# Eagle_CAD_XO_game.net
KiCad netlist of a schematic drawn in EAGLE
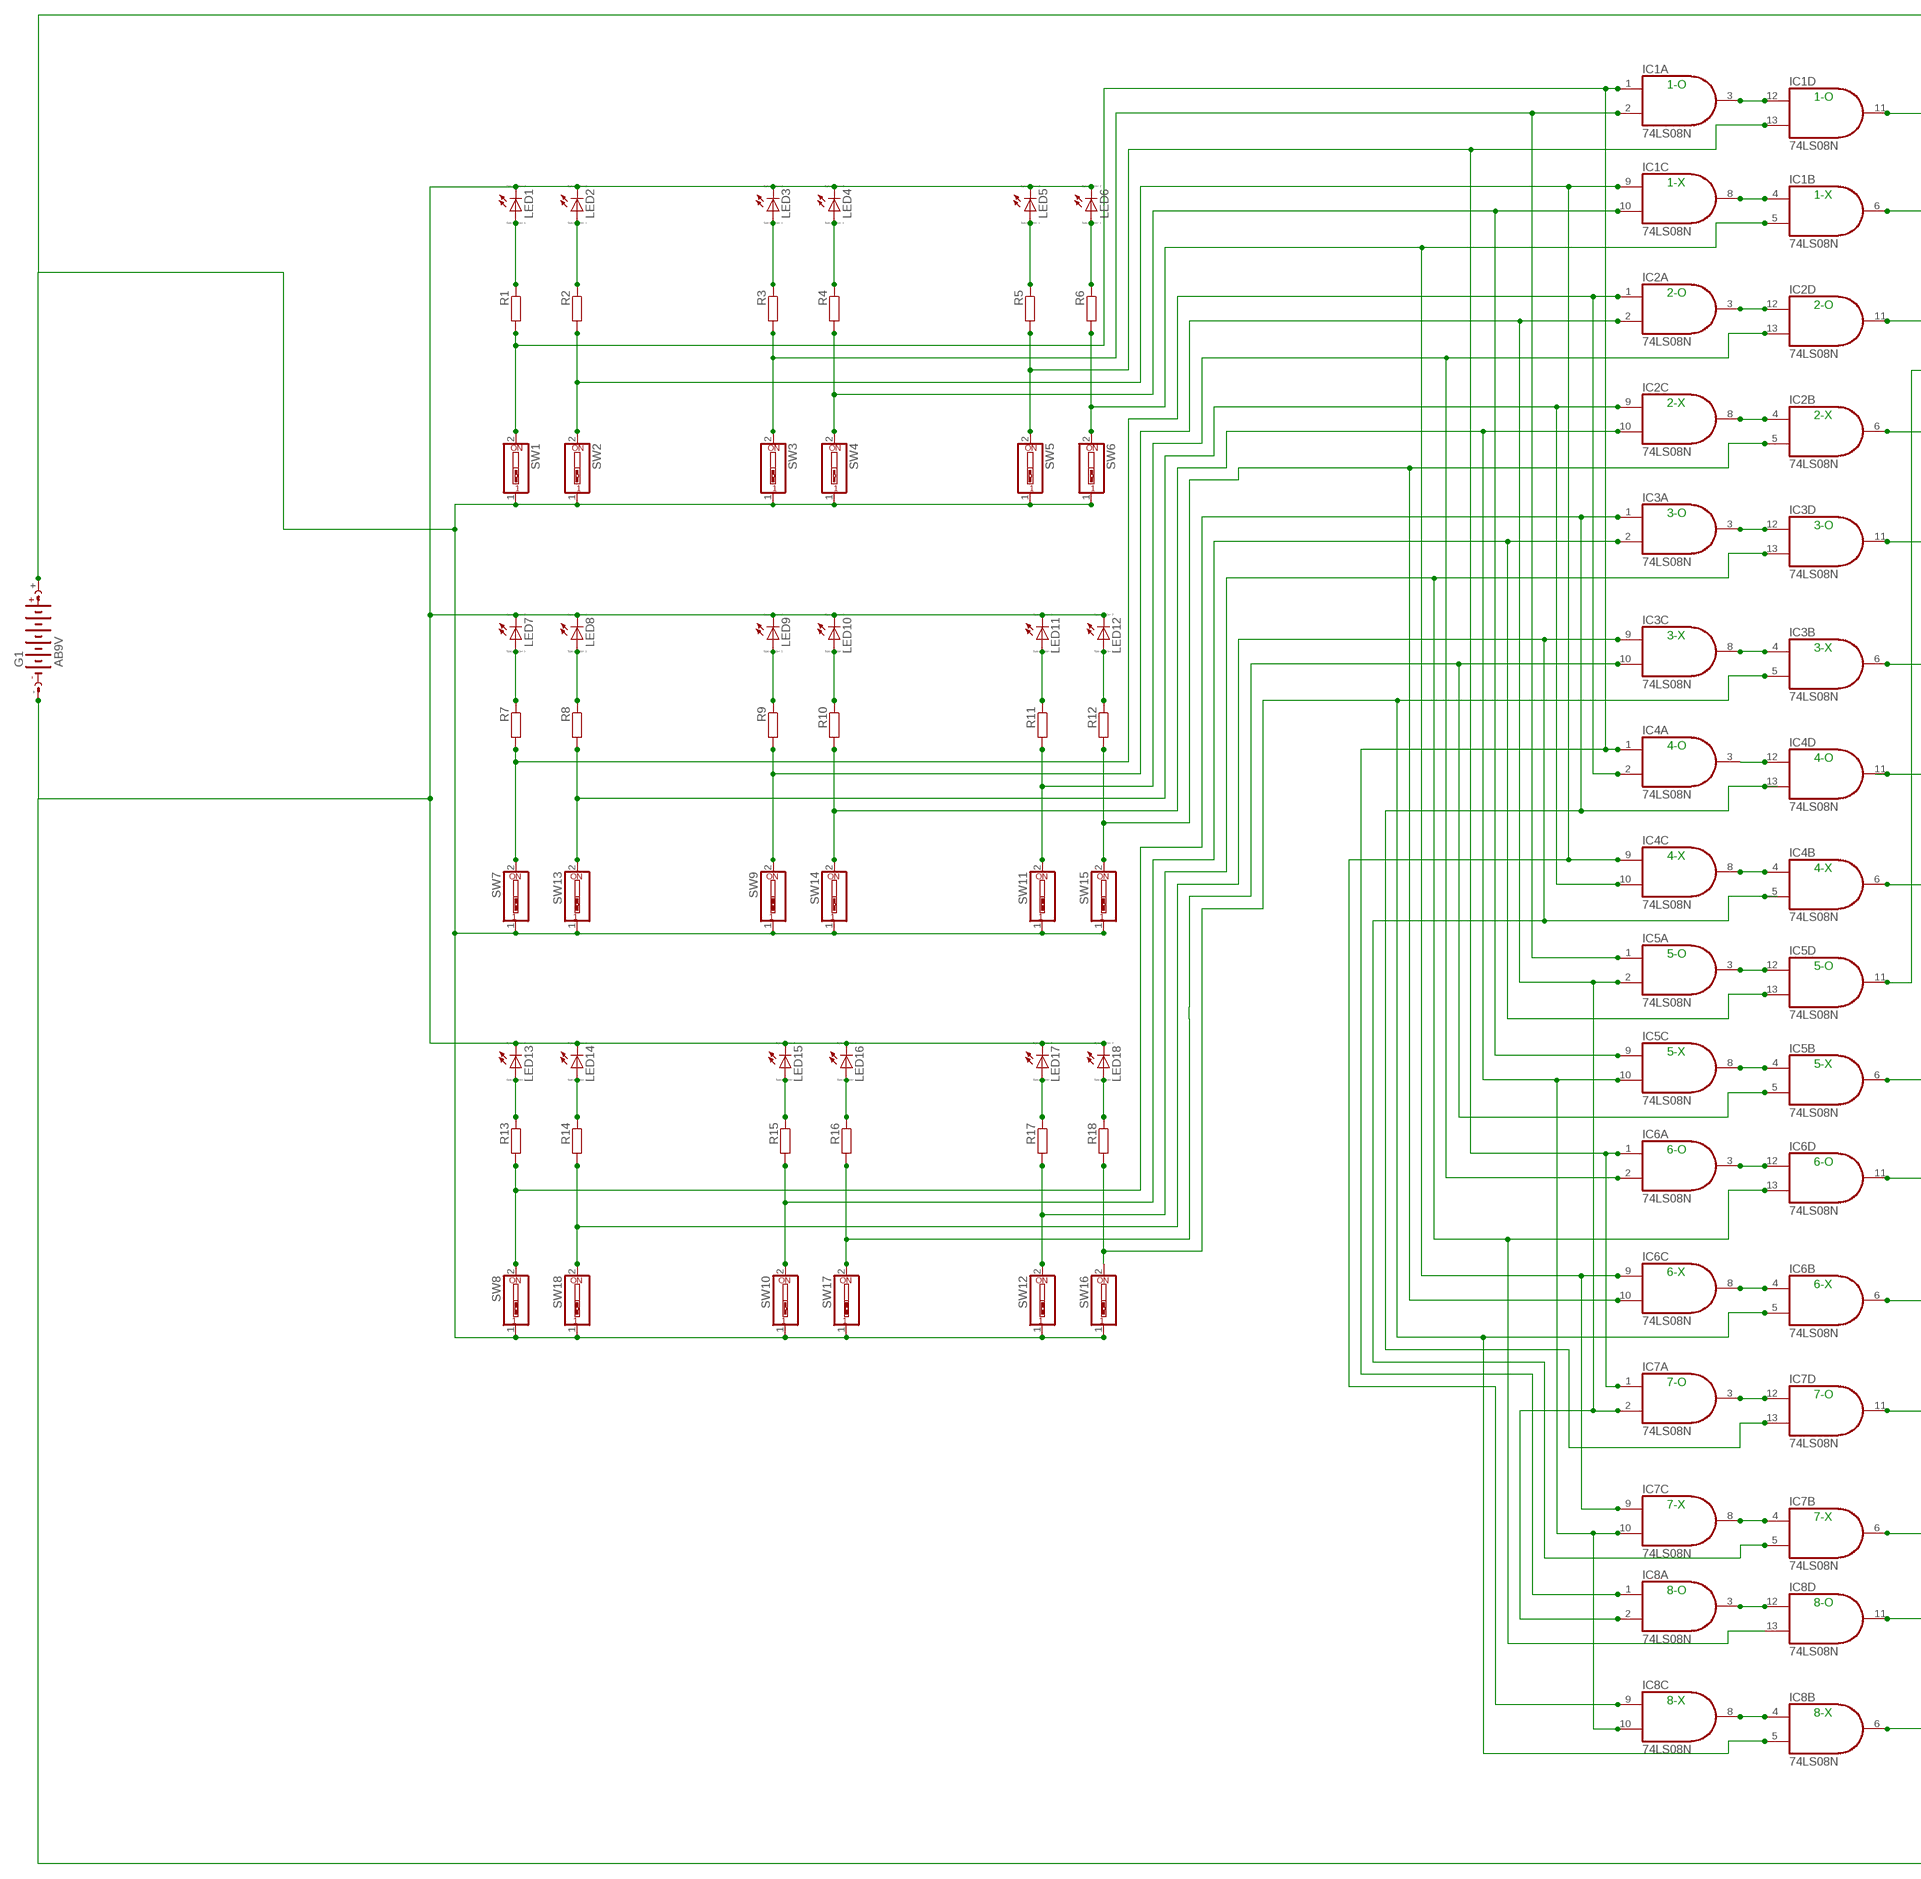
[diagram p0: schematic, sheet 1, part 1 of 2]
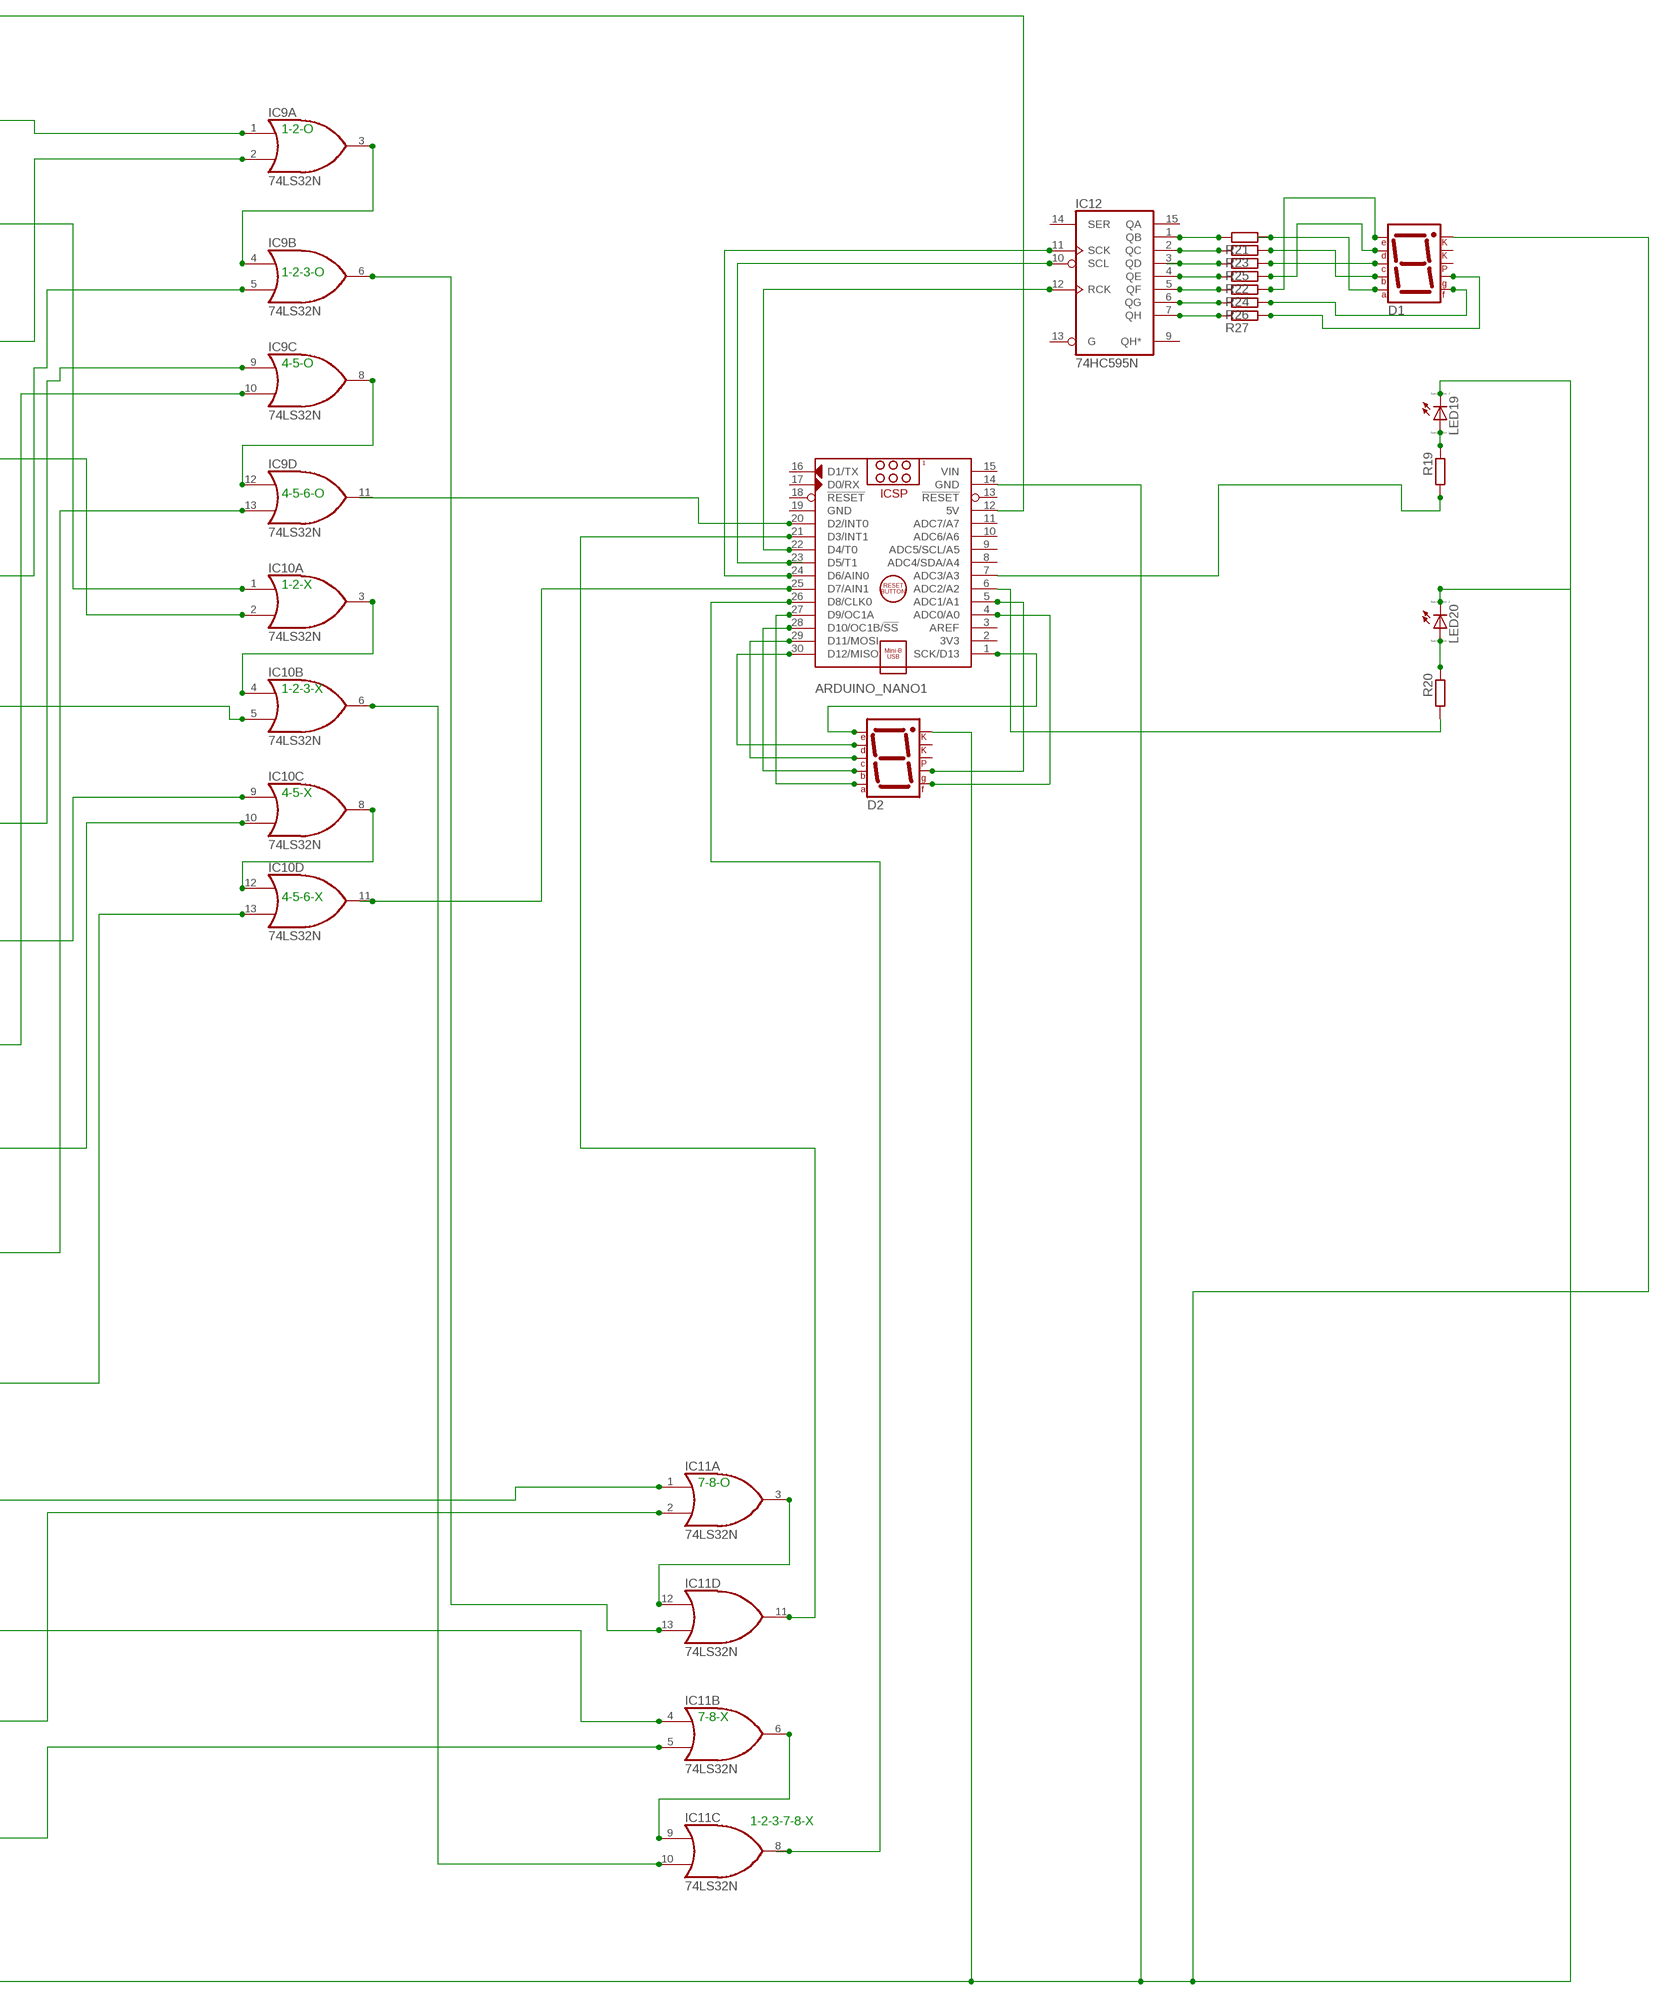
[diagram p1: schematic, sheet 1, part 2 of 2]

(export (version "E")
  (design (tool "Eeschema 10.0.6"))
  (components
    (comp (ref "ARDUINO_NANO1")
      (value "ARDUINO_NANO")
      (footprint "eagle-import:ARDUINO_NANO")
      (libsource (lib "eagle-import") (part "ARDUINO_NANO"))
    )
    (comp (ref "D1")
      (value "7SEG-CK")
      (footprint "eagle-import:7SEG-13")
      (libsource (lib "eagle-import") (part "7SEG-CK"))
    )
    (comp (ref "D2")
      (value "7SEG-CK")
      (footprint "eagle-import:7SEG-13")
      (libsource (lib "eagle-import") (part "7SEG-CK"))
    )
    (comp (ref "G1")
      (value "AB9V")
      (footprint "eagle-import:AB9V")
      (libsource (lib "eagle-import") (part "AB9V"))
    )
    (comp (ref "IC1")
      (value "74LS08N")
      (footprint "eagle-import:DIL14")
      (libsource (lib "eagle-import") (part "7408NLS"))
    )
    (comp (ref "IC2")
      (value "74LS08N")
      (footprint "eagle-import:DIL14")
      (libsource (lib "eagle-import") (part "7408NLS"))
    )
    (comp (ref "IC3")
      (value "74LS08N")
      (footprint "eagle-import:DIL14")
      (libsource (lib "eagle-import") (part "7408NLS"))
    )
    (comp (ref "IC4")
      (value "74LS08N")
      (footprint "eagle-import:DIL14")
      (libsource (lib "eagle-import") (part "7408NLS"))
    )
    (comp (ref "IC5")
      (value "74LS08N")
      (footprint "eagle-import:DIL14")
      (libsource (lib "eagle-import") (part "7408NLS"))
    )
    (comp (ref "IC6")
      (value "74LS08N")
      (footprint "eagle-import:DIL14")
      (libsource (lib "eagle-import") (part "7408NLS"))
    )
    (comp (ref "IC7")
      (value "74LS08N")
      (footprint "eagle-import:DIL14")
      (libsource (lib "eagle-import") (part "7408NLS"))
    )
    (comp (ref "IC8")
      (value "74LS08N")
      (footprint "eagle-import:DIL14")
      (libsource (lib "eagle-import") (part "7408NLS"))
    )
    (comp (ref "IC9")
      (value "74LS32N")
      (footprint "eagle-import:DIL14")
      (libsource (lib "eagle-import") (part "7432NLS"))
    )
    (comp (ref "IC10")
      (value "74LS32N")
      (footprint "eagle-import:DIL14")
      (libsource (lib "eagle-import") (part "7432NLS"))
    )
    (comp (ref "IC11")
      (value "74LS32N")
      (footprint "eagle-import:DIL14")
      (libsource (lib "eagle-import") (part "7432NLS"))
    )
    (comp (ref "IC12")
      (value "74HC595N")
      (footprint "eagle-import:DIL16")
      (libsource (lib "eagle-import") (part "74595NHC"))
    )
    (comp (ref "LED1")
      (value "LED_ELD260")
      (footprint "eagle-import:LED_LD260")
      (libsource (lib "eagle-import") (part "LED_ELD260"))
    )
    (comp (ref "LED2")
      (value "LED_ELD260")
      (footprint "eagle-import:LED_LD260")
      (libsource (lib "eagle-import") (part "LED_ELD260"))
    )
    (comp (ref "LED3")
      (value "LED_ELD260")
      (footprint "eagle-import:LED_LD260")
      (libsource (lib "eagle-import") (part "LED_ELD260"))
    )
    (comp (ref "LED4")
      (value "LED_ELD260")
      (footprint "eagle-import:LED_LD260")
      (libsource (lib "eagle-import") (part "LED_ELD260"))
    )
    (comp (ref "LED5")
      (value "LED_ELD260")
      (footprint "eagle-import:LED_LD260")
      (libsource (lib "eagle-import") (part "LED_ELD260"))
    )
    (comp (ref "LED6")
      (value "LED_ELD260")
      (footprint "eagle-import:LED_LD260")
      (libsource (lib "eagle-import") (part "LED_ELD260"))
    )
    (comp (ref "LED7")
      (value "LED_ELD260")
      (footprint "eagle-import:LED_LD260")
      (libsource (lib "eagle-import") (part "LED_ELD260"))
    )
    (comp (ref "LED8")
      (value "LED_ELD260")
      (footprint "eagle-import:LED_LD260")
      (libsource (lib "eagle-import") (part "LED_ELD260"))
    )
    (comp (ref "LED9")
      (value "LED_ELD260")
      (footprint "eagle-import:LED_LD260")
      (libsource (lib "eagle-import") (part "LED_ELD260"))
    )
    (comp (ref "LED10")
      (value "LED_ELD260")
      (footprint "eagle-import:LED_LD260")
      (libsource (lib "eagle-import") (part "LED_ELD260"))
    )
    (comp (ref "LED11")
      (value "LED_ELD260")
      (footprint "eagle-import:LED_LD260")
      (libsource (lib "eagle-import") (part "LED_ELD260"))
    )
    (comp (ref "LED12")
      (value "LED_ELD260")
      (footprint "eagle-import:LED_LD260")
      (libsource (lib "eagle-import") (part "LED_ELD260"))
    )
    (comp (ref "LED13")
      (value "LED_ELD260")
      (footprint "eagle-import:LED_LD260")
      (libsource (lib "eagle-import") (part "LED_ELD260"))
    )
    (comp (ref "LED14")
      (value "LED_ELD260")
      (footprint "eagle-import:LED_LD260")
      (libsource (lib "eagle-import") (part "LED_ELD260"))
    )
    (comp (ref "LED15")
      (value "LED_ELD260")
      (footprint "eagle-import:LED_LD260")
      (libsource (lib "eagle-import") (part "LED_ELD260"))
    )
    (comp (ref "LED16")
      (value "LED_ELD260")
      (footprint "eagle-import:LED_LD260")
      (libsource (lib "eagle-import") (part "LED_ELD260"))
    )
    (comp (ref "LED17")
      (value "LED_ELD260")
      (footprint "eagle-import:LED_LD260")
      (libsource (lib "eagle-import") (part "LED_ELD260"))
    )
    (comp (ref "LED18")
      (value "LED_ELD260")
      (footprint "eagle-import:LED_LD260")
      (libsource (lib "eagle-import") (part "LED_ELD260"))
    )
    (comp (ref "LED19")
      (value "LED_ELD260")
      (footprint "eagle-import:LED_LD260")
      (libsource (lib "eagle-import") (part "LED_ELD260"))
    )
    (comp (ref "LED20")
      (value "LED_ELD260")
      (footprint "eagle-import:LED_LD260")
      (libsource (lib "eagle-import") (part "LED_ELD260"))
    )
    (comp (ref "R1")
      (value "R-EU_0204/7")
      (footprint "eagle-import:0204_7")
      (libsource (lib "eagle-import") (part "R-EU_0204/7"))
    )
    (comp (ref "R2")
      (value "R-EU_0204/7")
      (footprint "eagle-import:0204_7")
      (libsource (lib "eagle-import") (part "R-EU_0204/7"))
    )
    (comp (ref "R3")
      (value "R-EU_0204/7")
      (footprint "eagle-import:0204_7")
      (libsource (lib "eagle-import") (part "R-EU_0204/7"))
    )
    (comp (ref "R4")
      (value "R-EU_0204/7")
      (footprint "eagle-import:0204_7")
      (libsource (lib "eagle-import") (part "R-EU_0204/7"))
    )
    (comp (ref "R5")
      (value "R-EU_0204/7")
      (footprint "eagle-import:0204_7")
      (libsource (lib "eagle-import") (part "R-EU_0204/7"))
    )
    (comp (ref "R6")
      (value "R-EU_0204/7")
      (footprint "eagle-import:0204_7")
      (libsource (lib "eagle-import") (part "R-EU_0204/7"))
    )
    (comp (ref "R7")
      (value "R-EU_0204/7")
      (footprint "eagle-import:0204_7")
      (libsource (lib "eagle-import") (part "R-EU_0204/7"))
    )
    (comp (ref "R8")
      (value "R-EU_0204/7")
      (footprint "eagle-import:0204_7")
      (libsource (lib "eagle-import") (part "R-EU_0204/7"))
    )
    (comp (ref "R9")
      (value "R-EU_0204/7")
      (footprint "eagle-import:0204_7")
      (libsource (lib "eagle-import") (part "R-EU_0204/7"))
    )
    (comp (ref "R10")
      (value "R-EU_0204/7")
      (footprint "eagle-import:0204_7")
      (libsource (lib "eagle-import") (part "R-EU_0204/7"))
    )
    (comp (ref "R11")
      (value "R-EU_0204/7")
      (footprint "eagle-import:0204_7")
      (libsource (lib "eagle-import") (part "R-EU_0204/7"))
    )
    (comp (ref "R12")
      (value "R-EU_0204/7")
      (footprint "eagle-import:0204_7")
      (libsource (lib "eagle-import") (part "R-EU_0204/7"))
    )
    (comp (ref "R13")
      (value "R-EU_0204/7")
      (footprint "eagle-import:0204_7")
      (libsource (lib "eagle-import") (part "R-EU_0204/7"))
    )
    (comp (ref "R14")
      (value "R-EU_0204/7")
      (footprint "eagle-import:0204_7")
      (libsource (lib "eagle-import") (part "R-EU_0204/7"))
    )
    (comp (ref "R15")
      (value "R-EU_0204/7")
      (footprint "eagle-import:0204_7")
      (libsource (lib "eagle-import") (part "R-EU_0204/7"))
    )
    (comp (ref "R16")
      (value "R-EU_0204/7")
      (footprint "eagle-import:0204_7")
      (libsource (lib "eagle-import") (part "R-EU_0204/7"))
    )
    (comp (ref "R17")
      (value "R-EU_0204/7")
      (footprint "eagle-import:0204_7")
      (libsource (lib "eagle-import") (part "R-EU_0204/7"))
    )
    (comp (ref "R18")
      (value "R-EU_0204/7")
      (footprint "eagle-import:0204_7")
      (libsource (lib "eagle-import") (part "R-EU_0204/7"))
    )
    (comp (ref "R19")
      (value "R-EU_0204/7")
      (footprint "eagle-import:0204_7")
      (libsource (lib "eagle-import") (part "R-EU_0204/7"))
    )
    (comp (ref "R20")
      (value "R-EU_0204/7")
      (footprint "eagle-import:0204_7")
      (libsource (lib "eagle-import") (part "R-EU_0204/7"))
    )
    (comp (ref "R21")
      (value "R-EU_0204/7")
      (footprint "eagle-import:0204_7")
      (libsource (lib "eagle-import") (part "R-EU_0204/7"))
    )
    (comp (ref "R22")
      (value "R-EU_0204/7")
      (footprint "eagle-import:0204_7")
      (libsource (lib "eagle-import") (part "R-EU_0204/7"))
    )
    (comp (ref "R23")
      (value "R-EU_0204/7")
      (footprint "eagle-import:0204_7")
      (libsource (lib "eagle-import") (part "R-EU_0204/7"))
    )
    (comp (ref "R24")
      (value "R-EU_0204/7")
      (footprint "eagle-import:0204_7")
      (libsource (lib "eagle-import") (part "R-EU_0204/7"))
    )
    (comp (ref "R25")
      (value "R-EU_0204/7")
      (footprint "eagle-import:0204_7")
      (libsource (lib "eagle-import") (part "R-EU_0204/7"))
    )
    (comp (ref "R26")
      (value "R-EU_0204/7")
      (footprint "eagle-import:0204_7")
      (libsource (lib "eagle-import") (part "R-EU_0204/7"))
    )
    (comp (ref "R27")
      (value "R-EU_0204/7")
      (footprint "eagle-import:0204_7")
      (libsource (lib "eagle-import") (part "R-EU_0204/7"))
    )
    (comp (ref "SW1")
      (value "SW_DIP-1")
      (footprint "eagle-import:EDG-01")
      (libsource (lib "eagle-import") (part "SW_DIP-1"))
    )
    (comp (ref "SW2")
      (value "SW_DIP-1")
      (footprint "eagle-import:EDG-01")
      (libsource (lib "eagle-import") (part "SW_DIP-1"))
    )
    (comp (ref "SW3")
      (value "SW_DIP-1")
      (footprint "eagle-import:EDG-01")
      (libsource (lib "eagle-import") (part "SW_DIP-1"))
    )
    (comp (ref "SW4")
      (value "SW_DIP-1")
      (footprint "eagle-import:EDG-01")
      (libsource (lib "eagle-import") (part "SW_DIP-1"))
    )
    (comp (ref "SW5")
      (value "SW_DIP-1")
      (footprint "eagle-import:EDG-01")
      (libsource (lib "eagle-import") (part "SW_DIP-1"))
    )
    (comp (ref "SW6")
      (value "SW_DIP-1")
      (footprint "eagle-import:EDG-01")
      (libsource (lib "eagle-import") (part "SW_DIP-1"))
    )
    (comp (ref "SW7")
      (value "SW_DIP-1")
      (footprint "eagle-import:EDG-01")
      (libsource (lib "eagle-import") (part "SW_DIP-1"))
    )
    (comp (ref "SW8")
      (value "SW_DIP-1")
      (footprint "eagle-import:EDG-01")
      (libsource (lib "eagle-import") (part "SW_DIP-1"))
    )
    (comp (ref "SW9")
      (value "SW_DIP-1")
      (footprint "eagle-import:EDG-01")
      (libsource (lib "eagle-import") (part "SW_DIP-1"))
    )
    (comp (ref "SW10")
      (value "SW_DIP-1")
      (footprint "eagle-import:EDG-01")
      (libsource (lib "eagle-import") (part "SW_DIP-1"))
    )
    (comp (ref "SW11")
      (value "SW_DIP-1")
      (footprint "eagle-import:EDG-01")
      (libsource (lib "eagle-import") (part "SW_DIP-1"))
    )
    (comp (ref "SW12")
      (value "SW_DIP-1")
      (footprint "eagle-import:EDG-01")
      (libsource (lib "eagle-import") (part "SW_DIP-1"))
    )
    (comp (ref "SW13")
      (value "SW_DIP-1")
      (footprint "eagle-import:EDG-01")
      (libsource (lib "eagle-import") (part "SW_DIP-1"))
    )
    (comp (ref "SW14")
      (value "SW_DIP-1")
      (footprint "eagle-import:EDG-01")
      (libsource (lib "eagle-import") (part "SW_DIP-1"))
    )
    (comp (ref "SW15")
      (value "SW_DIP-1")
      (footprint "eagle-import:EDG-01")
      (libsource (lib "eagle-import") (part "SW_DIP-1"))
    )
    (comp (ref "SW16")
      (value "SW_DIP-1")
      (footprint "eagle-import:EDG-01")
      (libsource (lib "eagle-import") (part "SW_DIP-1"))
    )
    (comp (ref "SW17")
      (value "SW_DIP-1")
      (footprint "eagle-import:EDG-01")
      (libsource (lib "eagle-import") (part "SW_DIP-1"))
    )
    (comp (ref "SW18")
      (value "SW_DIP-1")
      (footprint "eagle-import:EDG-01")
      (libsource (lib "eagle-import") (part "SW_DIP-1"))
    )
  )
  (nets
    (net (code "1") (name "/GND") (class "Default")
      (node (ref "ARDUINO_NANO1") (pin "19") (pinfunction "GND_19") (pintype "power_in"))
    )
    (net (code "2") (name "/VIN") (class "Default")
      (node (ref "ARDUINO_NANO1") (pin "15") (pinfunction "VIN_15") (pintype "power_in"))
    )
    (net (code "3") (name "Net-(ARDUINO_NANO1-5V)") (class "Default")
      (node (ref "ARDUINO_NANO1") (pin "12") (pinfunction "5V_12") (pintype "power_in"))
      (node (ref "G1") (pin "+") (pinfunction "+_+") (pintype "passive"))
      (node (ref "SW1") (pin "1") (pinfunction "1_1") (pintype "passive"))
      (node (ref "SW10") (pin "1") (pinfunction "1_1") (pintype "passive"))
      (node (ref "SW11") (pin "1") (pinfunction "1_1") (pintype "passive"))
      (node (ref "SW12") (pin "1") (pinfunction "1_1") (pintype "passive"))
      (node (ref "SW13") (pin "1") (pinfunction "1_1") (pintype "passive"))
      (node (ref "SW14") (pin "1") (pinfunction "1_1") (pintype "passive"))
      (node (ref "SW15") (pin "1") (pinfunction "1_1") (pintype "passive"))
      (node (ref "SW16") (pin "1") (pinfunction "1_1") (pintype "passive"))
      (node (ref "SW17") (pin "1") (pinfunction "1_1") (pintype "passive"))
      (node (ref "SW18") (pin "1") (pinfunction "1_1") (pintype "passive"))
      (node (ref "SW2") (pin "1") (pinfunction "1_1") (pintype "passive"))
      (node (ref "SW3") (pin "1") (pinfunction "1_1") (pintype "passive"))
      (node (ref "SW4") (pin "1") (pinfunction "1_1") (pintype "passive"))
      (node (ref "SW5") (pin "1") (pinfunction "1_1") (pintype "passive"))
      (node (ref "SW6") (pin "1") (pinfunction "1_1") (pintype "passive"))
      (node (ref "SW7") (pin "1") (pinfunction "1_1") (pintype "passive"))
      (node (ref "SW8") (pin "1") (pinfunction "1_1") (pintype "passive"))
      (node (ref "SW9") (pin "1") (pinfunction "1_1") (pintype "passive"))
    )
    (net (code "4") (name "Net-(ARDUINO_NANO1-ADC0{slash}A0)") (class "Default")
      (node (ref "ARDUINO_NANO1") (pin "4") (pinfunction "ADC0/A0_4") (pintype "bidirectional"))
      (node (ref "D2") (pin "9") (pinfunction "F_9") (pintype "passive"))
    )
    (net (code "5") (name "Net-(ARDUINO_NANO1-ADC1{slash}A1)") (class "Default")
      (node (ref "ARDUINO_NANO1") (pin "5") (pinfunction "ADC1/A1_5") (pintype "bidirectional"))
      (node (ref "D2") (pin "10") (pinfunction "G_10") (pintype "passive"))
    )
    (net (code "6") (name "Net-(ARDUINO_NANO1-ADC2{slash}A2)") (class "Default")
      (node (ref "ARDUINO_NANO1") (pin "6") (pinfunction "ADC2/A2_6") (pintype "bidirectional"))
      (node (ref "R20") (pin "2") (pinfunction "2_2") (pintype "passive"))
    )
    (net (code "7") (name "Net-(ARDUINO_NANO1-ADC3{slash}A3)") (class "Default")
      (node (ref "ARDUINO_NANO1") (pin "7") (pinfunction "ADC3/A3_7") (pintype "bidirectional"))
      (node (ref "R19") (pin "2") (pinfunction "2_2") (pintype "passive"))
    )
    (net (code "8") (name "Net-(ARDUINO_NANO1-D3{slash}INT1)") (class "Default")
      (node (ref "ARDUINO_NANO1") (pin "21") (pinfunction "D3/INT1_21") (pintype "bidirectional"))
      (node (ref "IC11") (pin "11") (pinfunction "O_11") (pintype "output"))
    )
    (net (code "9") (name "Net-(ARDUINO_NANO1-D4{slash}T0)") (class "Default")
      (node (ref "ARDUINO_NANO1") (pin "22") (pinfunction "D4/T0_22") (pintype "bidirectional"))
      (node (ref "IC12") (pin "12") (pinfunction "RCK_12") (pintype "input"))
    )
    (net (code "10") (name "Net-(ARDUINO_NANO1-D5{slash}T1)") (class "Default")
      (node (ref "ARDUINO_NANO1") (pin "23") (pinfunction "D5/T1_23") (pintype "bidirectional"))
      (node (ref "IC12") (pin "10") (pinfunction "SCL_10") (pintype "input"))
    )
    (net (code "11") (name "Net-(ARDUINO_NANO1-D6{slash}AIN0)") (class "Default")
      (node (ref "ARDUINO_NANO1") (pin "24") (pinfunction "D6/AIN0_24") (pintype "bidirectional"))
      (node (ref "IC12") (pin "11") (pinfunction "SCK_11") (pintype "input"))
    )
    (net (code "12") (name "Net-(ARDUINO_NANO1-D7{slash}AIN1)") (class "Default")
      (node (ref "ARDUINO_NANO1") (pin "25") (pinfunction "D7/AIN1_25") (pintype "bidirectional"))
      (node (ref "IC10") (pin "11") (pinfunction "O_11") (pintype "output"))
    )
    (net (code "13") (name "Net-(ARDUINO_NANO1-D8{slash}CLK0)") (class "Default")
      (node (ref "ARDUINO_NANO1") (pin "26") (pinfunction "D8/CLK0_26") (pintype "bidirectional"))
      (node (ref "IC11") (pin "8") (pinfunction "O_8") (pintype "output"))
    )
    (net (code "14") (name "Net-(ARDUINO_NANO1-D9{slash}OC1A)") (class "Default")
      (node (ref "ARDUINO_NANO1") (pin "27") (pinfunction "D9/OC1A_27") (pintype "bidirectional"))
      (node (ref "D2") (pin "7") (pinfunction "A_7") (pintype "passive"))
    )
    (net (code "15") (name "Net-(ARDUINO_NANO1-D10{slash}OC1B{slash}~{SS})") (class "Default")
      (node (ref "ARDUINO_NANO1") (pin "28") (pinfunction "D10/OC1B/~{SS}_28") (pintype "bidirectional"))
      (node (ref "D2") (pin "6") (pinfunction "B_6") (pintype "passive"))
    )
    (net (code "16") (name "Net-(ARDUINO_NANO1-D11{slash}MOSI)") (class "Default")
      (node (ref "ARDUINO_NANO1") (pin "29") (pinfunction "D11/MOSI_29") (pintype "bidirectional"))
      (node (ref "D2") (pin "4") (pinfunction "C_4") (pintype "passive"))
    )
    (net (code "17") (name "Net-(ARDUINO_NANO1-D12{slash}MISO)") (class "Default")
      (node (ref "ARDUINO_NANO1") (pin "30") (pinfunction "D12/MISO_30") (pintype "bidirectional"))
      (node (ref "D2") (pin "2") (pinfunction "D_2") (pintype "passive"))
    )
    (net (code "18") (name "Net-(ARDUINO_NANO1-SCK{slash}D13)") (class "Default")
      (node (ref "ARDUINO_NANO1") (pin "1") (pinfunction "SCK/D13_1") (pintype "bidirectional"))
      (node (ref "D2") (pin "1") (pinfunction "E_1") (pintype "passive"))
    )
    (net (code "19") (name "Net-(D1-A)") (class "Default")
      (node (ref "D1") (pin "7") (pinfunction "A_7") (pintype "passive"))
      (node (ref "R21") (pin "2") (pinfunction "2_2") (pintype "passive"))
    )
    (net (code "20") (name "Net-(D1-B)") (class "Default")
      (node (ref "D1") (pin "6") (pinfunction "B_6") (pintype "passive"))
      (node (ref "R23") (pin "2") (pinfunction "2_2") (pintype "passive"))
    )
    (net (code "21") (name "Net-(D1-C)") (class "Default")
      (node (ref "D1") (pin "4") (pinfunction "C_4") (pintype "passive"))
      (node (ref "R25") (pin "2") (pinfunction "2_2") (pintype "passive"))
    )
    (net (code "22") (name "Net-(D1-CK2)") (class "Default")
      (node (ref "ARDUINO_NANO1") (pin "14") (pinfunction "GND_14") (pintype "power_in"))
      (node (ref "D1") (pin "8") (pinfunction "CK2_8") (pintype "passive"))
      (node (ref "D2") (pin "8") (pinfunction "CK2_8") (pintype "passive"))
      (node (ref "G1") (pin "-") (pinfunction "-_-") (pintype "passive"))
      (node (ref "LED1") (pin "K") (pinfunction "C_K") (pintype "passive"))
      (node (ref "LED10") (pin "K") (pinfunction "C_K") (pintype "passive"))
      (node (ref "LED11") (pin "K") (pinfunction "C_K") (pintype "passive"))
      (node (ref "LED12") (pin "K") (pinfunction "C_K") (pintype "passive"))
      (node (ref "LED13") (pin "K") (pinfunction "C_K") (pintype "passive"))
      (node (ref "LED14") (pin "K") (pinfunction "C_K") (pintype "passive"))
      (node (ref "LED15") (pin "K") (pinfunction "C_K") (pintype "passive"))
      (node (ref "LED16") (pin "K") (pinfunction "C_K") (pintype "passive"))
      (node (ref "LED17") (pin "K") (pinfunction "C_K") (pintype "passive"))
      (node (ref "LED18") (pin "K") (pinfunction "C_K") (pintype "passive"))
      (node (ref "LED19") (pin "K") (pinfunction "C_K") (pintype "passive"))
      (node (ref "LED2") (pin "K") (pinfunction "C_K") (pintype "passive"))
      (node (ref "LED20") (pin "K") (pinfunction "C_K") (pintype "passive"))
      (node (ref "LED3") (pin "K") (pinfunction "C_K") (pintype "passive"))
      (node (ref "LED4") (pin "K") (pinfunction "C_K") (pintype "passive"))
      (node (ref "LED5") (pin "K") (pinfunction "C_K") (pintype "passive"))
      (node (ref "LED6") (pin "K") (pinfunction "C_K") (pintype "passive"))
      (node (ref "LED7") (pin "K") (pinfunction "C_K") (pintype "passive"))
      (node (ref "LED8") (pin "K") (pinfunction "C_K") (pintype "passive"))
      (node (ref "LED9") (pin "K") (pinfunction "C_K") (pintype "passive"))
    )
    (net (code "23") (name "Net-(D1-D)") (class "Default")
      (node (ref "D1") (pin "2") (pinfunction "D_2") (pintype "passive"))
      (node (ref "R22") (pin "2") (pinfunction "2_2") (pintype "passive"))
    )
    (net (code "24") (name "Net-(D1-E)") (class "Default")
      (node (ref "D1") (pin "1") (pinfunction "E_1") (pintype "passive"))
      (node (ref "R24") (pin "2") (pinfunction "2_2") (pintype "passive"))
    )
    (net (code "25") (name "Net-(D1-F)") (class "Default")
      (node (ref "D1") (pin "9") (pinfunction "F_9") (pintype "passive"))
      (node (ref "R26") (pin "2") (pinfunction "2_2") (pintype "passive"))
    )
    (net (code "26") (name "Net-(D1-G)") (class "Default")
      (node (ref "D1") (pin "10") (pinfunction "G_10") (pintype "passive"))
      (node (ref "R27") (pin "2") (pinfunction "2_2") (pintype "passive"))
    )
    (net (code "27") (name "Net-(IC1A-I0)") (class "Default")
      (node (ref "IC1") (pin "1") (pinfunction "I0_1") (pintype "input"))
      (node (ref "IC4") (pin "1") (pinfunction "I0_1") (pintype "input"))
      (node (ref "IC8") (pin "1") (pinfunction "I0_1") (pintype "input"))
      (node (ref "R1") (pin "2") (pinfunction "2_2") (pintype "passive"))
      (node (ref "SW1") (pin "2") (pinfunction "2_2") (pintype "passive"))
    )
    (net (code "28") (name "Net-(IC1A-I1)") (class "Default")
      (node (ref "IC1") (pin "2") (pinfunction "I1_2") (pintype "input"))
      (node (ref "IC5") (pin "1") (pinfunction "I0_1") (pintype "input"))
      (node (ref "R3") (pin "2") (pinfunction "2_2") (pintype "passive"))
      (node (ref "SW3") (pin "2") (pinfunction "2_2") (pintype "passive"))
    )
    (net (code "29") (name "Net-(IC1A-O)") (class "Default")
      (node (ref "IC1") (pin "12") (pinfunction "I0_12") (pintype "input"))
      (node (ref "IC1") (pin "3") (pinfunction "O_3") (pintype "output"))
    )
    (net (code "30") (name "Net-(IC1B-I0)") (class "Default")
      (node (ref "IC1") (pin "4") (pinfunction "I0_4") (pintype "input"))
      (node (ref "IC1") (pin "8") (pinfunction "O_8") (pintype "output"))
    )
    (net (code "31") (name "Net-(IC1B-I1)") (class "Default")
      (node (ref "IC1") (pin "5") (pinfunction "I1_5") (pintype "input"))
      (node (ref "IC6") (pin "9") (pinfunction "I0_9") (pintype "input"))
      (node (ref "IC7") (pin "9") (pinfunction "I0_9") (pintype "input"))
      (node (ref "R6") (pin "2") (pinfunction "2_2") (pintype "passive"))
      (node (ref "SW6") (pin "2") (pinfunction "2_2") (pintype "passive"))
    )
    (net (code "32") (name "Net-(IC1C-I0)") (class "Default")
      (node (ref "IC1") (pin "9") (pinfunction "I0_9") (pintype "input"))
      (node (ref "IC4") (pin "9") (pinfunction "I0_9") (pintype "input"))
      (node (ref "IC8") (pin "9") (pinfunction "I0_9") (pintype "input"))
      (node (ref "R2") (pin "2") (pinfunction "2_2") (pintype "passive"))
      (node (ref "SW2") (pin "2") (pinfunction "2_2") (pintype "passive"))
    )
    (net (code "33") (name "Net-(IC1C-I1)") (class "Default")
      (node (ref "IC1") (pin "10") (pinfunction "I1_10") (pintype "input"))
      (node (ref "IC5") (pin "9") (pinfunction "I0_9") (pintype "input"))
      (node (ref "R4") (pin "2") (pinfunction "2_2") (pintype "passive"))
      (node (ref "SW4") (pin "2") (pinfunction "2_2") (pintype "passive"))
    )
    (net (code "34") (name "Net-(IC1D-I1)") (class "Default")
      (node (ref "IC1") (pin "13") (pinfunction "I1_13") (pintype "input"))
      (node (ref "IC6") (pin "1") (pinfunction "I0_1") (pintype "input"))
      (node (ref "IC7") (pin "1") (pinfunction "I0_1") (pintype "input"))
      (node (ref "R5") (pin "2") (pinfunction "2_2") (pintype "passive"))
      (node (ref "SW5") (pin "2") (pinfunction "2_2") (pintype "passive"))
    )
    (net (code "35") (name "Net-(IC1D-O)") (class "Default")
      (node (ref "IC1") (pin "11") (pinfunction "O_11") (pintype "output"))
      (node (ref "IC9") (pin "1") (pinfunction "I0_1") (pintype "input"))
    )
    (net (code "36") (name "Net-(IC2A-I0)") (class "Default")
      (node (ref "IC2") (pin "1") (pinfunction "I0_1") (pintype "input"))
      (node (ref "IC4") (pin "2") (pinfunction "I1_2") (pintype "input"))
      (node (ref "R7") (pin "2") (pinfunction "2_2") (pintype "passive"))
      (node (ref "SW7") (pin "2") (pinfunction "2_2") (pintype "passive"))
    )
    (net (code "37") (name "Net-(IC2A-I1)") (class "Default")
      (node (ref "IC2") (pin "2") (pinfunction "I1_2") (pintype "input"))
      (node (ref "IC5") (pin "2") (pinfunction "I1_2") (pintype "input"))
      (node (ref "IC7") (pin "2") (pinfunction "I1_2") (pintype "input"))
      (node (ref "IC8") (pin "2") (pinfunction "I1_2") (pintype "input"))
      (node (ref "R9") (pin "2") (pinfunction "2_2") (pintype "passive"))
      (node (ref "SW9") (pin "2") (pinfunction "2_2") (pintype "passive"))
    )
    (net (code "38") (name "Net-(IC2A-O)") (class "Default")
      (node (ref "IC2") (pin "12") (pinfunction "I0_12") (pintype "input"))
      (node (ref "IC2") (pin "3") (pinfunction "O_3") (pintype "output"))
    )
    (net (code "39") (name "Net-(IC2B-I0)") (class "Default")
      (node (ref "IC2") (pin "4") (pinfunction "I0_4") (pintype "input"))
      (node (ref "IC2") (pin "8") (pinfunction "O_8") (pintype "output"))
    )
    (net (code "40") (name "Net-(IC2B-I1)") (class "Default")
      (node (ref "IC2") (pin "5") (pinfunction "I1_5") (pintype "input"))
      (node (ref "IC6") (pin "10") (pinfunction "I1_10") (pintype "input"))
      (node (ref "R12") (pin "2") (pinfunction "2_2") (pintype "passive"))
      (node (ref "SW15") (pin "2") (pinfunction "2_2") (pintype "passive"))
    )
    (net (code "41") (name "Net-(IC2C-I0)") (class "Default")
      (node (ref "IC2") (pin "9") (pinfunction "I0_9") (pintype "input"))
      (node (ref "IC4") (pin "10") (pinfunction "I1_10") (pintype "input"))
      (node (ref "R8") (pin "2") (pinfunction "2_2") (pintype "passive"))
      (node (ref "SW13") (pin "2") (pinfunction "2_2") (pintype "passive"))
    )
    (net (code "42") (name "Net-(IC2C-I1)") (class "Default")
      (node (ref "IC2") (pin "10") (pinfunction "I1_10") (pintype "input"))
      (node (ref "IC5") (pin "10") (pinfunction "I1_10") (pintype "input"))
      (node (ref "IC7") (pin "10") (pinfunction "I1_10") (pintype "input"))
      (node (ref "IC8") (pin "10") (pinfunction "I1_10") (pintype "input"))
      (node (ref "R10") (pin "2") (pinfunction "2_2") (pintype "passive"))
      (node (ref "SW14") (pin "2") (pinfunction "2_2") (pintype "passive"))
    )
    (net (code "43") (name "Net-(IC2D-I1)") (class "Default")
      (node (ref "IC2") (pin "13") (pinfunction "I1_13") (pintype "input"))
      (node (ref "IC6") (pin "2") (pinfunction "I1_2") (pintype "input"))
      (node (ref "R11") (pin "2") (pinfunction "2_2") (pintype "passive"))
      (node (ref "SW11") (pin "2") (pinfunction "2_2") (pintype "passive"))
    )
    (net (code "44") (name "Net-(IC2D-O)") (class "Default")
      (node (ref "IC2") (pin "11") (pinfunction "O_11") (pintype "output"))
      (node (ref "IC9") (pin "2") (pinfunction "I1_2") (pintype "input"))
    )
    (net (code "45") (name "Net-(IC3A-I0)") (class "Default")
      (node (ref "IC3") (pin "1") (pinfunction "I0_1") (pintype "input"))
      (node (ref "IC4") (pin "13") (pinfunction "I1_13") (pintype "input"))
      (node (ref "IC7") (pin "13") (pinfunction "I1_13") (pintype "input"))
      (node (ref "R13") (pin "2") (pinfunction "2_2") (pintype "passive"))
      (node (ref "SW8") (pin "2") (pinfunction "2_2") (pintype "passive"))
    )
    (net (code "46") (name "Net-(IC3A-I1)") (class "Default")
      (node (ref "IC3") (pin "2") (pinfunction "I1_2") (pintype "input"))
      (node (ref "IC5") (pin "13") (pinfunction "I1_13") (pintype "input"))
      (node (ref "R15") (pin "2") (pinfunction "2_2") (pintype "passive"))
      (node (ref "SW10") (pin "2") (pinfunction "2_2") (pintype "passive"))
    )
    (net (code "47") (name "Net-(IC3A-O)") (class "Default")
      (node (ref "IC3") (pin "12") (pinfunction "I0_12") (pintype "input"))
      (node (ref "IC3") (pin "3") (pinfunction "O_3") (pintype "output"))
    )
    (net (code "48") (name "Net-(IC3B-I0)") (class "Default")
      (node (ref "IC3") (pin "4") (pinfunction "I0_4") (pintype "input"))
      (node (ref "IC3") (pin "8") (pinfunction "O_8") (pintype "output"))
    )
    (net (code "49") (name "Net-(IC3B-I1)") (class "Default")
      (node (ref "IC3") (pin "5") (pinfunction "I1_5") (pintype "input"))
      (node (ref "IC6") (pin "5") (pinfunction "I1_5") (pintype "input"))
      (node (ref "IC8") (pin "5") (pinfunction "I1_5") (pintype "input"))
      (node (ref "R18") (pin "2") (pinfunction "2_2") (pintype "passive"))
      (node (ref "SW16") (pin "2") (pinfunction "2_2") (pintype "passive"))
    )
    (net (code "50") (name "Net-(IC3C-I0)") (class "Default")
      (node (ref "IC3") (pin "9") (pinfunction "I0_9") (pintype "input"))
      (node (ref "IC4") (pin "5") (pinfunction "I1_5") (pintype "input"))
      (node (ref "IC7") (pin "5") (pinfunction "I1_5") (pintype "input"))
      (node (ref "R14") (pin "2") (pinfunction "2_2") (pintype "passive"))
      (node (ref "SW18") (pin "2") (pinfunction "2_2") (pintype "passive"))
    )
    (net (code "51") (name "Net-(IC3C-I1)") (class "Default")
      (node (ref "IC3") (pin "10") (pinfunction "I1_10") (pintype "input"))
      (node (ref "IC5") (pin "5") (pinfunction "I1_5") (pintype "input"))
      (node (ref "R16") (pin "2") (pinfunction "2_2") (pintype "passive"))
      (node (ref "SW17") (pin "2") (pinfunction "2_2") (pintype "passive"))
    )
    (net (code "52") (name "Net-(IC3D-I1)") (class "Default")
      (node (ref "IC3") (pin "13") (pinfunction "I1_13") (pintype "input"))
      (node (ref "IC6") (pin "13") (pinfunction "I1_13") (pintype "input"))
      (node (ref "IC8") (pin "13") (pinfunction "I1_13") (pintype "input"))
      (node (ref "R17") (pin "2") (pinfunction "2_2") (pintype "passive"))
      (node (ref "SW12") (pin "2") (pinfunction "2_2") (pintype "passive"))
    )
    (net (code "53") (name "Net-(IC3D-O)") (class "Default")
      (node (ref "IC3") (pin "11") (pinfunction "O_11") (pintype "output"))
      (node (ref "IC9") (pin "5") (pinfunction "I1_5") (pintype "input"))
    )
    (net (code "54") (name "Net-(IC4A-O)") (class "Default")
      (node (ref "IC4") (pin "12") (pinfunction "I0_12") (pintype "input"))
      (node (ref "IC4") (pin "3") (pinfunction "O_3") (pintype "output"))
    )
    (net (code "55") (name "Net-(IC4B-I0)") (class "Default")
      (node (ref "IC4") (pin "4") (pinfunction "I0_4") (pintype "input"))
      (node (ref "IC4") (pin "8") (pinfunction "O_8") (pintype "output"))
    )
    (net (code "56") (name "Net-(IC4D-O)") (class "Default")
      (node (ref "IC4") (pin "11") (pinfunction "O_11") (pintype "output"))
      (node (ref "IC9") (pin "9") (pinfunction "I0_9") (pintype "input"))
    )
    (net (code "57") (name "Net-(IC5A-O)") (class "Default")
      (node (ref "IC5") (pin "12") (pinfunction "I0_12") (pintype "input"))
      (node (ref "IC5") (pin "3") (pinfunction "O_3") (pintype "output"))
    )
    (net (code "58") (name "Net-(IC5B-I0)") (class "Default")
      (node (ref "IC5") (pin "4") (pinfunction "I0_4") (pintype "input"))
      (node (ref "IC5") (pin "8") (pinfunction "O_8") (pintype "output"))
    )
    (net (code "59") (name "Net-(IC5D-O)") (class "Default")
      (node (ref "IC5") (pin "11") (pinfunction "O_11") (pintype "output"))
      (node (ref "IC9") (pin "10") (pinfunction "I1_10") (pintype "input"))
    )
    (net (code "60") (name "Net-(IC6A-O)") (class "Default")
      (node (ref "IC6") (pin "12") (pinfunction "I0_12") (pintype "input"))
      (node (ref "IC6") (pin "3") (pinfunction "O_3") (pintype "output"))
    )
    (net (code "61") (name "Net-(IC6B-I0)") (class "Default")
      (node (ref "IC6") (pin "4") (pinfunction "I0_4") (pintype "input"))
      (node (ref "IC6") (pin "8") (pinfunction "O_8") (pintype "output"))
    )
    (net (code "62") (name "Net-(IC6D-O)") (class "Default")
      (node (ref "IC6") (pin "11") (pinfunction "O_11") (pintype "output"))
      (node (ref "IC9") (pin "13") (pinfunction "I1_13") (pintype "input"))
    )
    (net (code "63") (name "Net-(IC7A-O)") (class "Default")
      (node (ref "IC7") (pin "12") (pinfunction "I0_12") (pintype "input"))
      (node (ref "IC7") (pin "3") (pinfunction "O_3") (pintype "output"))
    )
    (net (code "64") (name "Net-(IC7B-I0)") (class "Default")
      (node (ref "IC7") (pin "4") (pinfunction "I0_4") (pintype "input"))
      (node (ref "IC7") (pin "8") (pinfunction "O_8") (pintype "output"))
    )
    (net (code "65") (name "Net-(IC8A-O)") (class "Default")
      (node (ref "IC8") (pin "12") (pinfunction "I0_12") (pintype "input"))
      (node (ref "IC8") (pin "3") (pinfunction "O_3") (pintype "output"))
    )
    (net (code "66") (name "Net-(IC8B-I0)") (class "Default")
      (node (ref "IC8") (pin "4") (pinfunction "I0_4") (pintype "input"))
      (node (ref "IC8") (pin "8") (pinfunction "O_8") (pintype "output"))
    )
    (net (code "67") (name "Net-(IC9A-O)") (class "Default")
      (node (ref "IC9") (pin "3") (pinfunction "O_3") (pintype "output"))
      (node (ref "IC9") (pin "4") (pinfunction "I0_4") (pintype "input"))
    )
    (net (code "68") (name "Net-(IC9C-O)") (class "Default")
      (node (ref "IC9") (pin "12") (pinfunction "I0_12") (pintype "input"))
      (node (ref "IC9") (pin "8") (pinfunction "O_8") (pintype "output"))
    )
    (net (code "69") (name "Net-(IC10A-I0)") (class "Default")
      (node (ref "IC1") (pin "6") (pinfunction "O_6") (pintype "output"))
      (node (ref "IC10") (pin "1") (pinfunction "I0_1") (pintype "input"))
    )
    (net (code "70") (name "Net-(IC10A-I1)") (class "Default")
      (node (ref "IC10") (pin "2") (pinfunction "I1_2") (pintype "input"))
      (node (ref "IC2") (pin "6") (pinfunction "O_6") (pintype "output"))
    )
    (net (code "71") (name "Net-(IC10A-O)") (class "Default")
      (node (ref "IC10") (pin "3") (pinfunction "O_3") (pintype "output"))
      (node (ref "IC10") (pin "4") (pinfunction "I0_4") (pintype "input"))
    )
    (net (code "72") (name "Net-(IC10B-I1)") (class "Default")
      (node (ref "IC10") (pin "5") (pinfunction "I1_5") (pintype "input"))
      (node (ref "IC3") (pin "6") (pinfunction "O_6") (pintype "output"))
    )
    (net (code "73") (name "Net-(IC10B-O)") (class "Default")
      (node (ref "IC10") (pin "6") (pinfunction "O_6") (pintype "output"))
      (node (ref "IC11") (pin "10") (pinfunction "I1_10") (pintype "input"))
    )
    (net (code "74") (name "Net-(IC10C-I0)") (class "Default")
      (node (ref "IC10") (pin "9") (pinfunction "I0_9") (pintype "input"))
      (node (ref "IC4") (pin "6") (pinfunction "O_6") (pintype "output"))
    )
    (net (code "75") (name "Net-(IC10C-I1)") (class "Default")
      (node (ref "IC10") (pin "10") (pinfunction "I1_10") (pintype "input"))
      (node (ref "IC5") (pin "6") (pinfunction "O_6") (pintype "output"))
    )
    (net (code "76") (name "Net-(IC10C-O)") (class "Default")
      (node (ref "IC10") (pin "12") (pinfunction "I0_12") (pintype "input"))
      (node (ref "IC10") (pin "8") (pinfunction "O_8") (pintype "output"))
    )
    (net (code "77") (name "Net-(IC10D-I1)") (class "Default")
      (node (ref "IC10") (pin "13") (pinfunction "I1_13") (pintype "input"))
      (node (ref "IC6") (pin "6") (pinfunction "O_6") (pintype "output"))
    )
    (net (code "78") (name "Net-(IC11A-I0)") (class "Default")
      (node (ref "IC11") (pin "1") (pinfunction "I0_1") (pintype "input"))
      (node (ref "IC7") (pin "11") (pinfunction "O_11") (pintype "output"))
    )
    (net (code "79") (name "Net-(IC11A-I1)") (class "Default")
      (node (ref "IC11") (pin "2") (pinfunction "I1_2") (pintype "input"))
      (node (ref "IC8") (pin "11") (pinfunction "O_11") (pintype "output"))
    )
    (net (code "80") (name "Net-(IC11A-O)") (class "Default")
      (node (ref "IC11") (pin "12") (pinfunction "I0_12") (pintype "input"))
      (node (ref "IC11") (pin "3") (pinfunction "O_3") (pintype "output"))
    )
    (net (code "81") (name "Net-(IC11B-I0)") (class "Default")
      (node (ref "IC11") (pin "4") (pinfunction "I0_4") (pintype "input"))
      (node (ref "IC7") (pin "6") (pinfunction "O_6") (pintype "output"))
    )
    (net (code "82") (name "Net-(IC11B-I1)") (class "Default")
      (node (ref "IC11") (pin "5") (pinfunction "I1_5") (pintype "input"))
      (node (ref "IC8") (pin "6") (pinfunction "O_6") (pintype "output"))
    )
    (net (code "83") (name "Net-(IC11B-O)") (class "Default")
      (node (ref "IC11") (pin "6") (pinfunction "O_6") (pintype "output"))
      (node (ref "IC11") (pin "9") (pinfunction "I0_9") (pintype "input"))
    )
    (net (code "84") (name "Net-(IC11D-I1)") (class "Default")
      (node (ref "IC11") (pin "13") (pinfunction "I1_13") (pintype "input"))
      (node (ref "IC9") (pin "6") (pinfunction "O_6") (pintype "output"))
    )
    (net (code "85") (name "Net-(IC12A-QB)") (class "Default")
      (node (ref "IC12") (pin "1") (pinfunction "QB_1") (pintype "tri_state"))
      (node (ref "R21") (pin "1") (pinfunction "1_1") (pintype "passive"))
    )
    (net (code "86") (name "Net-(IC12A-QC)") (class "Default")
      (node (ref "IC12") (pin "2") (pinfunction "QC_2") (pintype "tri_state"))
      (node (ref "R23") (pin "1") (pinfunction "1_1") (pintype "passive"))
    )
    (net (code "87") (name "Net-(IC12A-QD)") (class "Default")
      (node (ref "IC12") (pin "3") (pinfunction "QD_3") (pintype "tri_state"))
      (node (ref "R25") (pin "1") (pinfunction "1_1") (pintype "passive"))
    )
    (net (code "88") (name "Net-(IC12A-QE)") (class "Default")
      (node (ref "IC12") (pin "4") (pinfunction "QE_4") (pintype "tri_state"))
      (node (ref "R22") (pin "1") (pinfunction "1_1") (pintype "passive"))
    )
    (net (code "89") (name "Net-(IC12A-QF)") (class "Default")
      (node (ref "IC12") (pin "5") (pinfunction "QF_5") (pintype "tri_state"))
      (node (ref "R24") (pin "1") (pinfunction "1_1") (pintype "passive"))
    )
    (net (code "90") (name "Net-(IC12A-QG)") (class "Default")
      (node (ref "IC12") (pin "6") (pinfunction "QG_6") (pintype "tri_state"))
      (node (ref "R26") (pin "1") (pinfunction "1_1") (pintype "passive"))
    )
    (net (code "91") (name "Net-(IC12A-QH)") (class "Default")
      (node (ref "IC12") (pin "7") (pinfunction "QH_7") (pintype "tri_state"))
      (node (ref "R27") (pin "1") (pinfunction "1_1") (pintype "passive"))
    )
    (net (code "92") (name "Net-(LED1-PadA)") (class "Default")
      (node (ref "LED1") (pin "A") (pinfunction "A_A") (pintype "passive"))
      (node (ref "R1") (pin "1") (pinfunction "1_1") (pintype "passive"))
    )
    (net (code "93") (name "Net-(LED2-PadA)") (class "Default")
      (node (ref "LED2") (pin "A") (pinfunction "A_A") (pintype "passive"))
      (node (ref "R2") (pin "1") (pinfunction "1_1") (pintype "passive"))
    )
    (net (code "94") (name "Net-(LED3-PadA)") (class "Default")
      (node (ref "LED3") (pin "A") (pinfunction "A_A") (pintype "passive"))
      (node (ref "R3") (pin "1") (pinfunction "1_1") (pintype "passive"))
    )
    (net (code "95") (name "Net-(LED4-PadA)") (class "Default")
      (node (ref "LED4") (pin "A") (pinfunction "A_A") (pintype "passive"))
      (node (ref "R4") (pin "1") (pinfunction "1_1") (pintype "passive"))
    )
    (net (code "96") (name "Net-(LED5-PadA)") (class "Default")
      (node (ref "LED5") (pin "A") (pinfunction "A_A") (pintype "passive"))
      (node (ref "R5") (pin "1") (pinfunction "1_1") (pintype "passive"))
    )
    (net (code "97") (name "Net-(LED6-PadA)") (class "Default")
      (node (ref "LED6") (pin "A") (pinfunction "A_A") (pintype "passive"))
      (node (ref "R6") (pin "1") (pinfunction "1_1") (pintype "passive"))
    )
    (net (code "98") (name "Net-(LED7-PadA)") (class "Default")
      (node (ref "LED7") (pin "A") (pinfunction "A_A") (pintype "passive"))
      (node (ref "R7") (pin "1") (pinfunction "1_1") (pintype "passive"))
    )
    (net (code "99") (name "Net-(LED8-PadA)") (class "Default")
      (node (ref "LED8") (pin "A") (pinfunction "A_A") (pintype "passive"))
      (node (ref "R8") (pin "1") (pinfunction "1_1") (pintype "passive"))
    )
    (net (code "100") (name "Net-(LED9-PadA)") (class "Default")
      (node (ref "LED9") (pin "A") (pinfunction "A_A") (pintype "passive"))
      (node (ref "R9") (pin "1") (pinfunction "1_1") (pintype "passive"))
    )
    (net (code "101") (name "Net-(LED10-PadA)") (class "Default")
      (node (ref "LED10") (pin "A") (pinfunction "A_A") (pintype "passive"))
      (node (ref "R10") (pin "1") (pinfunction "1_1") (pintype "passive"))
    )
    (net (code "102") (name "Net-(LED11-PadA)") (class "Default")
      (node (ref "LED11") (pin "A") (pinfunction "A_A") (pintype "passive"))
      (node (ref "R11") (pin "1") (pinfunction "1_1") (pintype "passive"))
    )
    (net (code "103") (name "Net-(LED12-PadA)") (class "Default")
      (node (ref "LED12") (pin "A") (pinfunction "A_A") (pintype "passive"))
      (node (ref "R12") (pin "1") (pinfunction "1_1") (pintype "passive"))
    )
    (net (code "104") (name "Net-(LED13-PadA)") (class "Default")
      (node (ref "LED13") (pin "A") (pinfunction "A_A") (pintype "passive"))
      (node (ref "R13") (pin "1") (pinfunction "1_1") (pintype "passive"))
    )
    (net (code "105") (name "Net-(LED14-PadA)") (class "Default")
      (node (ref "LED14") (pin "A") (pinfunction "A_A") (pintype "passive"))
      (node (ref "R14") (pin "1") (pinfunction "1_1") (pintype "passive"))
    )
    (net (code "106") (name "Net-(LED15-PadA)") (class "Default")
      (node (ref "LED15") (pin "A") (pinfunction "A_A") (pintype "passive"))
      (node (ref "R15") (pin "1") (pinfunction "1_1") (pintype "passive"))
    )
    (net (code "107") (name "Net-(LED16-PadA)") (class "Default")
      (node (ref "LED16") (pin "A") (pinfunction "A_A") (pintype "passive"))
      (node (ref "R16") (pin "1") (pinfunction "1_1") (pintype "passive"))
    )
    (net (code "108") (name "Net-(LED17-PadA)") (class "Default")
      (node (ref "LED17") (pin "A") (pinfunction "A_A") (pintype "passive"))
      (node (ref "R17") (pin "1") (pinfunction "1_1") (pintype "passive"))
    )
    (net (code "109") (name "Net-(LED18-PadA)") (class "Default")
      (node (ref "LED18") (pin "A") (pinfunction "A_A") (pintype "passive"))
      (node (ref "R18") (pin "1") (pinfunction "1_1") (pintype "passive"))
    )
    (net (code "110") (name "Net-(LED19-PadA)") (class "Default")
      (node (ref "LED19") (pin "A") (pinfunction "A_A") (pintype "passive"))
      (node (ref "R19") (pin "1") (pinfunction "1_1") (pintype "passive"))
    )
    (net (code "111") (name "Net-(LED20-PadA)") (class "Default")
      (node (ref "LED20") (pin "A") (pinfunction "A_A") (pintype "passive"))
      (node (ref "R20") (pin "1") (pinfunction "1_1") (pintype "passive"))
    )
    (net (code "112") (name "unconnected-(ARDUINO_NANO1-3V3-Pad2)") (class "Default")
      (node (ref "ARDUINO_NANO1") (pin "2") (pinfunction "3V3_2") (pintype "output"))
    )
    (net (code "113") (name "unconnected-(ARDUINO_NANO1-ADC4{slash}SDA{slash}A4-Pad8)") (class "Default")
      (node (ref "ARDUINO_NANO1") (pin "8") (pinfunction "ADC4/SDA/A4_8") (pintype "bidirectional"))
    )
    (net (code "114") (name "unconnected-(ARDUINO_NANO1-ADC5{slash}SCL{slash}A5-Pad9)") (class "Default")
      (node (ref "ARDUINO_NANO1") (pin "9") (pinfunction "ADC5/SCL/A5_9") (pintype "bidirectional"))
    )
    (net (code "115") (name "unconnected-(ARDUINO_NANO1-ADC6{slash}A6-Pad10)") (class "Default")
      (node (ref "ARDUINO_NANO1") (pin "10") (pinfunction "ADC6/A6_10") (pintype "bidirectional"))
    )
    (net (code "116") (name "unconnected-(ARDUINO_NANO1-ADC7{slash}A7-Pad11)") (class "Default")
      (node (ref "ARDUINO_NANO1") (pin "11") (pinfunction "ADC7/A7_11") (pintype "bidirectional"))
    )
    (net (code "117") (name "unconnected-(ARDUINO_NANO1-AREF-Pad3)") (class "Default")
      (node (ref "ARDUINO_NANO1") (pin "3") (pinfunction "AREF_3") (pintype "input"))
    )
    (net (code "118") (name "unconnected-(ARDUINO_NANO1-D0{slash}RX-Pad17)") (class "Default")
      (node (ref "ARDUINO_NANO1") (pin "17") (pinfunction "D0/RX_17") (pintype "bidirectional"))
    )
    (net (code "119") (name "unconnected-(ARDUINO_NANO1-D1{slash}TX-Pad16)") (class "Default")
      (node (ref "ARDUINO_NANO1") (pin "16") (pinfunction "D1/TX_16") (pintype "bidirectional"))
    )
    (net (code "120") (name "unconnected-(ARDUINO_NANO1-D2{slash}INT0-Pad20)") (class "Default")
      (node (ref "ARDUINO_NANO1") (pin "20") (pinfunction "D2/INT0_20") (pintype "bidirectional"))
    )
    (net (code "121") (name "unconnected-(ARDUINO_NANO1-~{RESET}-Pad13)") (class "Default")
      (node (ref "ARDUINO_NANO1") (pin "13") (pinfunction "~{RESET}_13") (pintype "input"))
    )
    (net (code "122") (name "unconnected-(ARDUINO_NANO1-~{RESET}-Pad18)") (class "Default")
      (node (ref "ARDUINO_NANO1") (pin "18") (pinfunction "~{RESET}_18") (pintype "input"))
    )
    (net (code "123") (name "unconnected-(D1-CK1-Pad3)") (class "Default")
      (node (ref "D1") (pin "3") (pinfunction "CK1_3") (pintype "passive"))
    )
    (net (code "124") (name "unconnected-(D1-DP-Pad5)") (class "Default")
      (node (ref "D1") (pin "5") (pinfunction "DP_5") (pintype "passive"))
    )
    (net (code "125") (name "unconnected-(D2-CK1-Pad3)") (class "Default")
      (node (ref "D2") (pin "3") (pinfunction "CK1_3") (pintype "passive"))
    )
    (net (code "126") (name "unconnected-(D2-DP-Pad5)") (class "Default")
      (node (ref "D2") (pin "5") (pinfunction "DP_5") (pintype "passive"))
    )
    (net (code "127") (name "unconnected-(IC9D-O-Pad11)") (class "Default")
      (node (ref "IC9") (pin "11") (pinfunction "O_11") (pintype "output"))
    )
    (net (code "128") (name "unconnected-(IC12A-G-Pad13)") (class "Default")
      (node (ref "IC12") (pin "13") (pinfunction "G_13") (pintype "input"))
    )
    (net (code "129") (name "unconnected-(IC12A-QA-Pad15)") (class "Default")
      (node (ref "IC12") (pin "15") (pinfunction "QA_15") (pintype "tri_state"))
    )
    (net (code "130") (name "unconnected-(IC12A-QH*-Pad9)") (class "Default")
      (node (ref "IC12") (pin "9") (pinfunction "QH*_9") (pintype "tri_state"))
    )
    (net (code "131") (name "unconnected-(IC12A-SER-Pad14)") (class "Default")
      (node (ref "IC12") (pin "14") (pinfunction "SER_14") (pintype "input"))
    )
  )
)
